# Key-HT16K23.net
KiCad netlist of a schematic drawn in Altium Designer
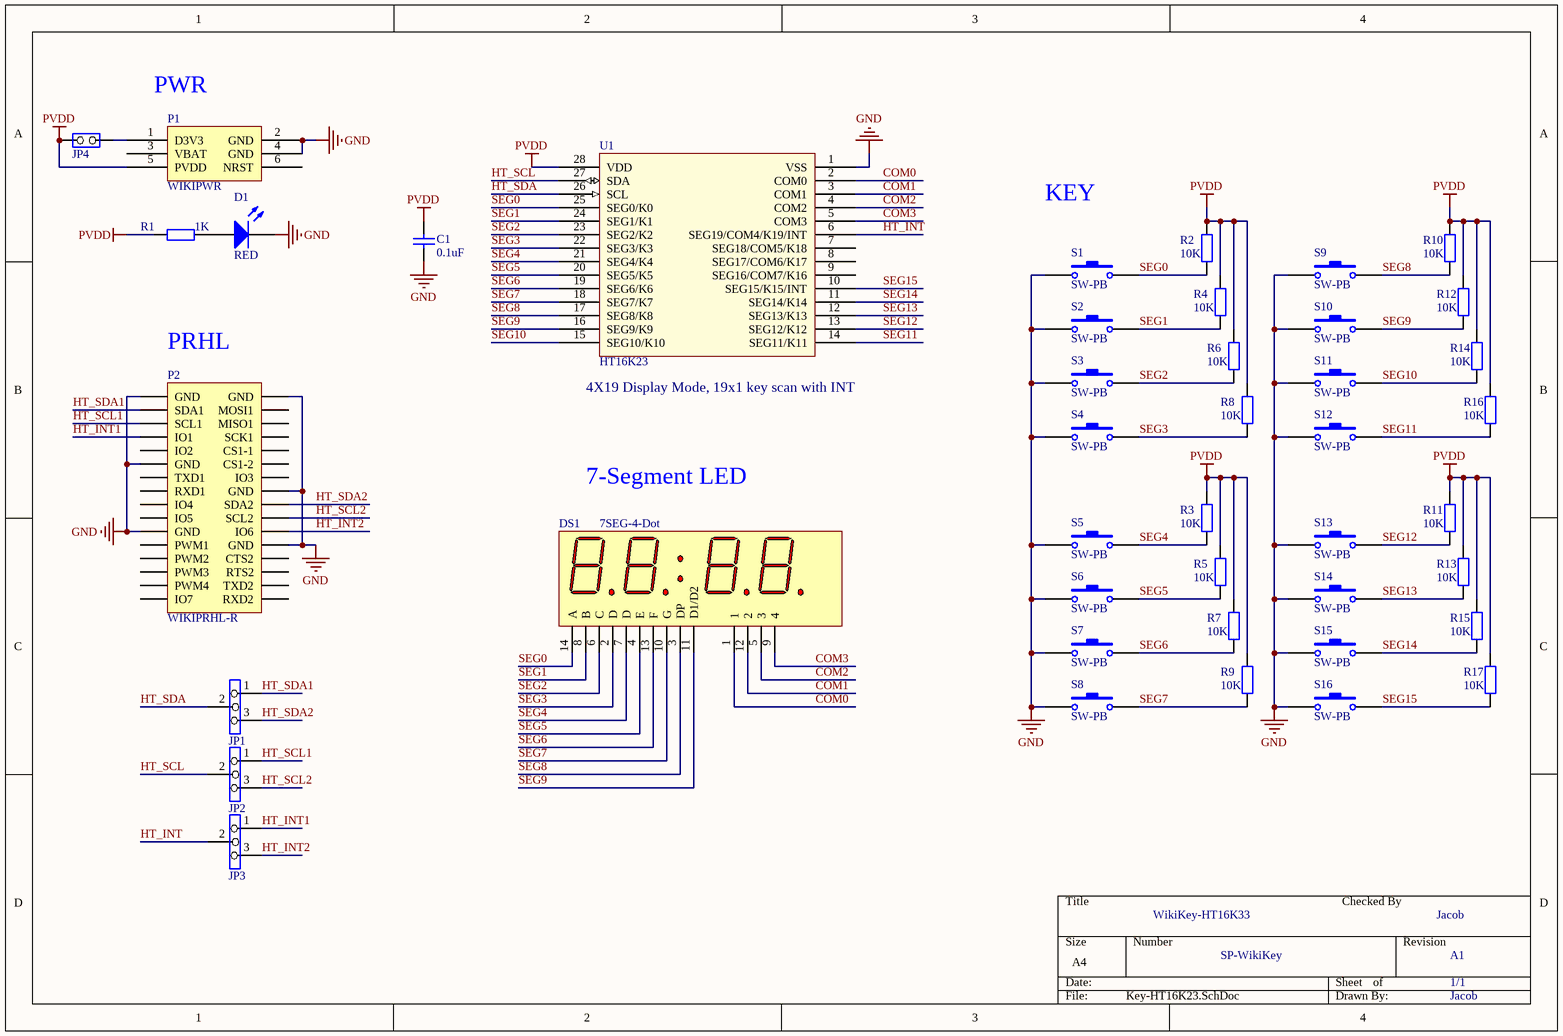
[diagram p0: Key-HT16K23.SchDoc]

(export (version "E")
  (design (tool "Eeschema 10.0.6"))
  (components
    (comp (ref "C1")
      (value "0.1uF")
      (footprint "0603M")
      (description "Capacitor")
      (fields (field (name "PUBLISHER") "Altium Limited"))
      (libsource (lib "Miscellaneous Devices") (part "Cap"))
    )
    (comp (ref "D1")
      (value "RED")
      (footprint "0603pn")
      (description "Typical INFRARED GaAs LED")
      (fields (field (name "PUBLISHER") "Altium Limited"))
      (libsource (lib "Miscellaneous Devices") (part "LED0"))
    )
    (comp (ref "DS1")
      (value "7SEG-4-Dot")
      (footprint "7SGLED-4-Dot-0.28")
      (description "Black Surface HER 7-Segment Display")
      (fields (field (name "PUBLISHER") "Altium Limited"))
      (libsource (lib "Misc") (part "7SEG-4-Dot"))
    )
    (comp (ref "JP1") (value "Jumper3") (footprint "HDR1X3/2.00mm") (libsource (lib "Misc") (part "Jumper3")))
    (comp (ref "JP2") (value "Jumper3") (footprint "HDR1X3/2.00mm") (libsource (lib "Misc") (part "Jumper3")))
    (comp (ref "JP3") (value "Jumper3") (footprint "HDR1X3/2.00mm") (libsource (lib "Misc") (part "Jumper3")))
    (comp (ref "JP4")
      (value "Jumper2-2")
      (footprint "JP2_SMD")
      (description "Jumper2")
      (libsource (lib "Misc") (part "Jumper2-2"))
    )
    (comp (ref "P1")
      (value "WIKIPWR")
      (footprint "WIKIPWR-6P")
      (description "PWR HDR")
      (libsource (lib "Connector") (part "WIKIPWR"))
    )
    (comp (ref "P2")
      (value "WIKIPRHL-R")
      (footprint "WIKIPRHL-R")
      (description "Header, 16-Pin, Dual row")
      (fields (field (name "PUBLISHER") "Altium Limited"))
      (libsource (lib "Connector") (part "WIKIPRHL-R"))
    )
    (comp (ref "R1")
      (value "1K")
      (footprint "0603M")
      (description "Resistor")
      (fields (field (name "PUBLISHER") "Altium Limited"))
      (libsource (lib "") (part "Res2_1"))
    )
    (comp (ref "R2")
      (value "10K")
      (footprint "0603M")
      (description "Resistor")
      (fields (field (name "PUBLISHER") "Altium Limited"))
      (libsource (lib "Miscellaneous Devices") (part "Res2"))
    )
    (comp (ref "R3")
      (value "10K")
      (footprint "0603M")
      (description "Resistor")
      (fields (field (name "PUBLISHER") "Altium Limited"))
      (libsource (lib "Miscellaneous Devices") (part "Res2"))
    )
    (comp (ref "R4")
      (value "10K")
      (footprint "0603M")
      (description "Resistor")
      (fields (field (name "PUBLISHER") "Altium Limited"))
      (libsource (lib "Miscellaneous Devices") (part "Res2"))
    )
    (comp (ref "R5")
      (value "10K")
      (footprint "0603M")
      (description "Resistor")
      (fields (field (name "PUBLISHER") "Altium Limited"))
      (libsource (lib "Miscellaneous Devices") (part "Res2"))
    )
    (comp (ref "R6")
      (value "10K")
      (footprint "0603M")
      (description "Resistor")
      (fields (field (name "PUBLISHER") "Altium Limited"))
      (libsource (lib "Miscellaneous Devices") (part "Res2"))
    )
    (comp (ref "R7")
      (value "10K")
      (footprint "0603M")
      (description "Resistor")
      (fields (field (name "PUBLISHER") "Altium Limited"))
      (libsource (lib "Miscellaneous Devices") (part "Res2"))
    )
    (comp (ref "R8")
      (value "10K")
      (footprint "0603M")
      (description "Resistor")
      (fields (field (name "PUBLISHER") "Altium Limited"))
      (libsource (lib "Miscellaneous Devices") (part "Res2"))
    )
    (comp (ref "R9")
      (value "10K")
      (footprint "0603M")
      (description "Resistor")
      (fields (field (name "PUBLISHER") "Altium Limited"))
      (libsource (lib "Miscellaneous Devices") (part "Res2"))
    )
    (comp (ref "R10")
      (value "10K")
      (footprint "0603M")
      (description "Resistor")
      (fields (field (name "PUBLISHER") "Altium Limited"))
      (libsource (lib "Miscellaneous Devices") (part "Res2"))
    )
    (comp (ref "R11")
      (value "10K")
      (footprint "0603M")
      (description "Resistor")
      (fields (field (name "PUBLISHER") "Altium Limited"))
      (libsource (lib "Miscellaneous Devices") (part "Res2"))
    )
    (comp (ref "R12")
      (value "10K")
      (footprint "0603M")
      (description "Resistor")
      (fields (field (name "PUBLISHER") "Altium Limited"))
      (libsource (lib "Miscellaneous Devices") (part "Res2"))
    )
    (comp (ref "R13")
      (value "10K")
      (footprint "0603M")
      (description "Resistor")
      (fields (field (name "PUBLISHER") "Altium Limited"))
      (libsource (lib "Miscellaneous Devices") (part "Res2"))
    )
    (comp (ref "R14")
      (value "10K")
      (footprint "0603M")
      (description "Resistor")
      (fields (field (name "PUBLISHER") "Altium Limited"))
      (libsource (lib "Miscellaneous Devices") (part "Res2"))
    )
    (comp (ref "R15")
      (value "10K")
      (footprint "0603M")
      (description "Resistor")
      (fields (field (name "PUBLISHER") "Altium Limited"))
      (libsource (lib "Miscellaneous Devices") (part "Res2"))
    )
    (comp (ref "R16")
      (value "10K")
      (footprint "0603M")
      (description "Resistor")
      (fields (field (name "PUBLISHER") "Altium Limited"))
      (libsource (lib "Miscellaneous Devices") (part "Res2"))
    )
    (comp (ref "R17")
      (value "10K")
      (footprint "0603M")
      (description "Resistor")
      (fields (field (name "PUBLISHER") "Altium Limited"))
      (libsource (lib "Miscellaneous Devices") (part "Res2"))
    )
    (comp (ref "S1")
      (value "SW-PB")
      (footprint "KEY-4.5X4.5-SMD")
      (description "Switch")
      (fields (field (name "PUBLISHER") "Altium Limited"))
      (libsource (lib "CT107D_SUDA") (part "SW-PB"))
    )
    (comp (ref "S2")
      (value "SW-PB")
      (footprint "KEY-4.5X4.5-SMD")
      (description "Switch")
      (fields (field (name "PUBLISHER") "Altium Limited"))
      (libsource (lib "CT107D_SUDA") (part "SW-PB"))
    )
    (comp (ref "S3")
      (value "SW-PB")
      (footprint "KEY-4.5X4.5-SMD")
      (description "Switch")
      (fields (field (name "PUBLISHER") "Altium Limited"))
      (libsource (lib "CT107D_SUDA") (part "SW-PB"))
    )
    (comp (ref "S4")
      (value "SW-PB")
      (footprint "KEY-4.5X4.5-SMD")
      (description "Switch")
      (fields (field (name "PUBLISHER") "Altium Limited"))
      (libsource (lib "CT107D_SUDA") (part "SW-PB"))
    )
    (comp (ref "S5")
      (value "SW-PB")
      (footprint "KEY-4.5X4.5-SMD")
      (description "Switch")
      (fields (field (name "PUBLISHER") "Altium Limited"))
      (libsource (lib "CT107D_SUDA") (part "SW-PB"))
    )
    (comp (ref "S6")
      (value "SW-PB")
      (footprint "KEY-4.5X4.5-SMD")
      (description "Switch")
      (fields (field (name "PUBLISHER") "Altium Limited"))
      (libsource (lib "CT107D_SUDA") (part "SW-PB"))
    )
    (comp (ref "S7")
      (value "SW-PB")
      (footprint "KEY-4.5X4.5-SMD")
      (description "Switch")
      (fields (field (name "PUBLISHER") "Altium Limited"))
      (libsource (lib "CT107D_SUDA") (part "SW-PB"))
    )
    (comp (ref "S8")
      (value "SW-PB")
      (footprint "KEY-4.5X4.5-SMD")
      (description "Switch")
      (fields (field (name "PUBLISHER") "Altium Limited"))
      (libsource (lib "CT107D_SUDA") (part "SW-PB"))
    )
    (comp (ref "S9")
      (value "SW-PB")
      (footprint "KEY-4.5X4.5-SMD")
      (description "Switch")
      (fields (field (name "PUBLISHER") "Altium Limited"))
      (libsource (lib "CT107D_SUDA") (part "SW-PB"))
    )
    (comp (ref "S10")
      (value "SW-PB")
      (footprint "KEY-4.5X4.5-SMD")
      (description "Switch")
      (fields (field (name "PUBLISHER") "Altium Limited"))
      (libsource (lib "CT107D_SUDA") (part "SW-PB"))
    )
    (comp (ref "S11")
      (value "SW-PB")
      (footprint "KEY-4.5X4.5-SMD")
      (description "Switch")
      (fields (field (name "PUBLISHER") "Altium Limited"))
      (libsource (lib "CT107D_SUDA") (part "SW-PB"))
    )
    (comp (ref "S12")
      (value "SW-PB")
      (footprint "KEY-4.5X4.5-SMD")
      (description "Switch")
      (fields (field (name "PUBLISHER") "Altium Limited"))
      (libsource (lib "CT107D_SUDA") (part "SW-PB"))
    )
    (comp (ref "S13")
      (value "SW-PB")
      (footprint "KEY-4.5X4.5-SMD")
      (description "Switch")
      (fields (field (name "PUBLISHER") "Altium Limited"))
      (libsource (lib "CT107D_SUDA") (part "SW-PB"))
    )
    (comp (ref "S14")
      (value "SW-PB")
      (footprint "KEY-4.5X4.5-SMD")
      (description "Switch")
      (fields (field (name "PUBLISHER") "Altium Limited"))
      (libsource (lib "CT107D_SUDA") (part "SW-PB"))
    )
    (comp (ref "S15")
      (value "SW-PB")
      (footprint "KEY-4.5X4.5-SMD")
      (description "Switch")
      (fields (field (name "PUBLISHER") "Altium Limited"))
      (libsource (lib "CT107D_SUDA") (part "SW-PB"))
    )
    (comp (ref "S16")
      (value "SW-PB")
      (footprint "KEY-4.5X4.5-SMD")
      (description "Switch")
      (fields (field (name "PUBLISHER") "Altium Limited"))
      (libsource (lib "CT107D_SUDA") (part "SW-PB"))
    )
    (comp (ref "U1")
      (value "HT16K23")
      (footprint "SO28_M")
      (description "LCD Driver with keyscan")
      (libsource (lib "Logic") (part "HT16K23"))
    )
  )
  (nets
    (net (code "1") (name "/COM0") (class "Default")
      (node (ref "DS1") (pin "1") (pinfunction "1_1") (pintype "passive"))
      (node (ref "U1") (pin "2") (pinfunction "COM0_2") (pintype "passive"))
    )
    (net (code "2") (name "/COM1") (class "Default")
      (node (ref "DS1") (pin "12") (pinfunction "2_12") (pintype "passive"))
      (node (ref "U1") (pin "3") (pinfunction "COM1_3") (pintype "passive"))
    )
    (net (code "3") (name "/COM2") (class "Default")
      (node (ref "DS1") (pin "5") (pinfunction "3_5") (pintype "passive"))
      (node (ref "U1") (pin "4") (pinfunction "COM2_4") (pintype "passive"))
    )
    (net (code "4") (name "/COM3") (class "Default")
      (node (ref "DS1") (pin "9") (pinfunction "4_9") (pintype "passive"))
      (node (ref "U1") (pin "5") (pinfunction "COM3_5") (pintype "passive"))
    )
    (net (code "5") (name "/HT_INT") (class "Default")
      (node (ref "JP3") (pin "2") (pintype "passive"))
      (node (ref "U1") (pin "6") (pinfunction "SEG19/COM4/K19/INT_6") (pintype "passive"))
    )
    (net (code "6") (name "/HT_INT1") (class "Default")
      (node (ref "JP3") (pin "1") (pintype "passive"))
      (node (ref "P2") (pin "7") (pinfunction "IO1_7") (pintype "passive"))
    )
    (net (code "7") (name "/HT_INT2") (class "Default")
      (node (ref "JP3") (pin "3") (pintype "passive"))
      (node (ref "P2") (pin "22") (pinfunction "IO6_22") (pintype "passive"))
    )
    (net (code "8") (name "/HT_SCL") (class "Default")
      (node (ref "JP2") (pin "2") (pintype "passive"))
      (node (ref "U1") (pin "27") (pinfunction "SDA_27") (pintype "bidirectional"))
    )
    (net (code "9") (name "/HT_SCL1") (class "Default")
      (node (ref "JP2") (pin "1") (pintype "passive"))
      (node (ref "P2") (pin "5") (pinfunction "SCL1_5") (pintype "passive"))
    )
    (net (code "10") (name "/HT_SCL2") (class "Default")
      (node (ref "JP2") (pin "3") (pintype "passive"))
      (node (ref "P2") (pin "20") (pinfunction "SCL2_20") (pintype "passive"))
    )
    (net (code "11") (name "/HT_SDA") (class "Default")
      (node (ref "JP1") (pin "2") (pintype "passive"))
      (node (ref "U1") (pin "26") (pinfunction "SCL_26") (pintype "input"))
    )
    (net (code "12") (name "/HT_SDA1") (class "Default")
      (node (ref "JP1") (pin "1") (pintype "passive"))
      (node (ref "P2") (pin "3") (pinfunction "SDA1_3") (pintype "passive"))
    )
    (net (code "13") (name "/HT_SDA2") (class "Default")
      (node (ref "JP1") (pin "3") (pintype "passive"))
      (node (ref "P2") (pin "18") (pinfunction "SDA2_18") (pintype "passive"))
    )
    (net (code "14") (name "/SEG0") (class "Default")
      (node (ref "DS1") (pin "14") (pinfunction "A_14") (pintype "passive"))
      (node (ref "R2") (pin "2") (pinfunction "2_2") (pintype "passive"))
      (node (ref "S1") (pin "2") (pinfunction "2_2") (pintype "passive"))
      (node (ref "U1") (pin "25") (pinfunction "SEG0/K0_25") (pintype "passive"))
    )
    (net (code "15") (name "/SEG1") (class "Default")
      (node (ref "DS1") (pin "8") (pinfunction "B_8") (pintype "passive"))
      (node (ref "R4") (pin "2") (pinfunction "2_2") (pintype "passive"))
      (node (ref "S2") (pin "2") (pinfunction "2_2") (pintype "passive"))
      (node (ref "U1") (pin "24") (pinfunction "SEG1/K1_24") (pintype "passive"))
    )
    (net (code "16") (name "/SEG2") (class "Default")
      (node (ref "DS1") (pin "6") (pinfunction "C_6") (pintype "passive"))
      (node (ref "R6") (pin "2") (pinfunction "2_2") (pintype "passive"))
      (node (ref "S3") (pin "2") (pinfunction "2_2") (pintype "passive"))
      (node (ref "U1") (pin "23") (pinfunction "SEG2/K2_23") (pintype "passive"))
    )
    (net (code "17") (name "/SEG3") (class "Default")
      (node (ref "DS1") (pin "2") (pinfunction "D_2") (pintype "passive"))
      (node (ref "R8") (pin "2") (pinfunction "2_2") (pintype "passive"))
      (node (ref "S4") (pin "2") (pinfunction "2_2") (pintype "passive"))
      (node (ref "U1") (pin "22") (pinfunction "SEG3/K3_22") (pintype "passive"))
    )
    (net (code "18") (name "/SEG4") (class "Default")
      (node (ref "DS1") (pin "7") (pinfunction "D_7") (pintype "passive"))
      (node (ref "R3") (pin "2") (pinfunction "2_2") (pintype "passive"))
      (node (ref "S5") (pin "2") (pinfunction "2_2") (pintype "passive"))
      (node (ref "U1") (pin "21") (pinfunction "SEG4/K4_21") (pintype "passive"))
    )
    (net (code "19") (name "/SEG5") (class "Default")
      (node (ref "DS1") (pin "4") (pinfunction "E_4") (pintype "passive"))
      (node (ref "R5") (pin "2") (pinfunction "2_2") (pintype "passive"))
      (node (ref "S6") (pin "2") (pinfunction "2_2") (pintype "passive"))
      (node (ref "U1") (pin "20") (pinfunction "SEG5/K5_20") (pintype "passive"))
    )
    (net (code "20") (name "/SEG6") (class "Default")
      (node (ref "DS1") (pin "13") (pinfunction "F_13") (pintype "passive"))
      (node (ref "R7") (pin "2") (pinfunction "2_2") (pintype "passive"))
      (node (ref "S7") (pin "2") (pinfunction "2_2") (pintype "passive"))
      (node (ref "U1") (pin "19") (pinfunction "SEG6/K6_19") (pintype "passive"))
    )
    (net (code "21") (name "/SEG7") (class "Default")
      (node (ref "DS1") (pin "10") (pinfunction "G_10") (pintype "passive"))
      (node (ref "R9") (pin "2") (pinfunction "2_2") (pintype "passive"))
      (node (ref "S8") (pin "2") (pinfunction "2_2") (pintype "passive"))
      (node (ref "U1") (pin "18") (pinfunction "SEG7/K7_18") (pintype "passive"))
    )
    (net (code "22") (name "/SEG8") (class "Default")
      (node (ref "DS1") (pin "3") (pinfunction "DP_3") (pintype "passive"))
      (node (ref "R10") (pin "2") (pinfunction "2_2") (pintype "passive"))
      (node (ref "S9") (pin "2") (pinfunction "2_2") (pintype "passive"))
      (node (ref "U1") (pin "17") (pinfunction "SEG8/K8_17") (pintype "passive"))
    )
    (net (code "23") (name "/SEG9") (class "Default")
      (node (ref "DS1") (pin "11") (pinfunction "D1/D2_11") (pintype "passive"))
      (node (ref "R12") (pin "2") (pinfunction "2_2") (pintype "passive"))
      (node (ref "S10") (pin "2") (pinfunction "2_2") (pintype "passive"))
      (node (ref "U1") (pin "16") (pinfunction "SEG9/K9_16") (pintype "passive"))
    )
    (net (code "24") (name "/SEG10") (class "Default")
      (node (ref "R14") (pin "2") (pinfunction "2_2") (pintype "passive"))
      (node (ref "S11") (pin "2") (pinfunction "2_2") (pintype "passive"))
      (node (ref "U1") (pin "15") (pinfunction "SEG10/K10_15") (pintype "passive"))
    )
    (net (code "25") (name "/SEG11") (class "Default")
      (node (ref "R16") (pin "2") (pinfunction "2_2") (pintype "passive"))
      (node (ref "S12") (pin "2") (pinfunction "2_2") (pintype "passive"))
      (node (ref "U1") (pin "14") (pinfunction "SEG11/K11_14") (pintype "passive"))
    )
    (net (code "26") (name "/SEG12") (class "Default")
      (node (ref "R11") (pin "2") (pinfunction "2_2") (pintype "passive"))
      (node (ref "S13") (pin "2") (pinfunction "2_2") (pintype "passive"))
      (node (ref "U1") (pin "13") (pinfunction "SEG12/K12_13") (pintype "passive"))
    )
    (net (code "27") (name "/SEG13") (class "Default")
      (node (ref "R13") (pin "2") (pinfunction "2_2") (pintype "passive"))
      (node (ref "S14") (pin "2") (pinfunction "2_2") (pintype "passive"))
      (node (ref "U1") (pin "12") (pinfunction "SEG13/K13_12") (pintype "passive"))
    )
    (net (code "28") (name "/SEG14") (class "Default")
      (node (ref "R15") (pin "2") (pinfunction "2_2") (pintype "passive"))
      (node (ref "S15") (pin "2") (pinfunction "2_2") (pintype "passive"))
      (node (ref "U1") (pin "11") (pinfunction "SEG14/K14_11") (pintype "passive"))
    )
    (net (code "29") (name "/SEG15") (class "Default")
      (node (ref "R17") (pin "2") (pinfunction "2_2") (pintype "passive"))
      (node (ref "S16") (pin "2") (pinfunction "2_2") (pintype "passive"))
      (node (ref "U1") (pin "10") (pinfunction "SEG15/K15/INT_10") (pintype "passive"))
    )
    (net (code "30") (name "GND") (class "Default")
      (node (ref "C1") (pin "1") (pinfunction "1_1") (pintype "passive"))
      (node (ref "D1") (pin "2") (pinfunction "K_2") (pintype "passive"))
      (node (ref "P1") (pin "2") (pinfunction "GND_2") (pintype "passive"))
      (node (ref "P1") (pin "4") (pinfunction "GND_4") (pintype "passive"))
      (node (ref "P2") (pin "1") (pinfunction "GND_1") (pintype "passive"))
      (node (ref "P2") (pin "11") (pinfunction "GND_11") (pintype "passive"))
      (node (ref "P2") (pin "16") (pinfunction "GND_16") (pintype "passive"))
      (node (ref "P2") (pin "2") (pinfunction "GND_2") (pintype "passive"))
      (node (ref "P2") (pin "21") (pinfunction "GND_21") (pintype "passive"))
      (node (ref "P2") (pin "24") (pinfunction "GND_24") (pintype "passive"))
      (node (ref "S1") (pin "1") (pinfunction "1_1") (pintype "passive"))
      (node (ref "S10") (pin "1") (pinfunction "1_1") (pintype "passive"))
      (node (ref "S11") (pin "1") (pinfunction "1_1") (pintype "passive"))
      (node (ref "S12") (pin "1") (pinfunction "1_1") (pintype "passive"))
      (node (ref "S13") (pin "1") (pinfunction "1_1") (pintype "passive"))
      (node (ref "S14") (pin "1") (pinfunction "1_1") (pintype "passive"))
      (node (ref "S15") (pin "1") (pinfunction "1_1") (pintype "passive"))
      (node (ref "S16") (pin "1") (pinfunction "1_1") (pintype "passive"))
      (node (ref "S2") (pin "1") (pinfunction "1_1") (pintype "passive"))
      (node (ref "S3") (pin "1") (pinfunction "1_1") (pintype "passive"))
      (node (ref "S4") (pin "1") (pinfunction "1_1") (pintype "passive"))
      (node (ref "S5") (pin "1") (pinfunction "1_1") (pintype "passive"))
      (node (ref "S6") (pin "1") (pinfunction "1_1") (pintype "passive"))
      (node (ref "S7") (pin "1") (pinfunction "1_1") (pintype "passive"))
      (node (ref "S8") (pin "1") (pinfunction "1_1") (pintype "passive"))
      (node (ref "S9") (pin "1") (pinfunction "1_1") (pintype "passive"))
      (node (ref "U1") (pin "1") (pinfunction "VSS_1") (pintype "power_in"))
    )
    (net (code "31") (name "Net-(D1-A)") (class "Default")
      (node (ref "D1") (pin "1") (pinfunction "A_1") (pintype "passive"))
      (node (ref "R1") (pin "1") (pinfunction "1_1") (pintype "passive"))
    )
    (net (code "32") (name "Net-(JP4-COMMON)") (class "Default")
      (node (ref "JP4") (pin "1") (pinfunction "COMMON_1") (pintype "passive"))
      (node (ref "P1") (pin "1") (pinfunction "D3V3_1") (pintype "passive"))
    )
    (net (code "33") (name "PVDD") (class "Default")
      (node (ref "C1") (pin "2") (pinfunction "2_2") (pintype "passive"))
      (node (ref "JP4") (pin "2") (pinfunction "NO_2") (pintype "passive"))
      (node (ref "P1") (pin "5") (pinfunction "PVDD_5") (pintype "passive"))
      (node (ref "R1") (pin "2") (pinfunction "2_2") (pintype "passive"))
      (node (ref "R10") (pin "1") (pinfunction "1_1") (pintype "passive"))
      (node (ref "R11") (pin "1") (pinfunction "1_1") (pintype "passive"))
      (node (ref "R12") (pin "1") (pinfunction "1_1") (pintype "passive"))
      (node (ref "R13") (pin "1") (pinfunction "1_1") (pintype "passive"))
      (node (ref "R14") (pin "1") (pinfunction "1_1") (pintype "passive"))
      (node (ref "R15") (pin "1") (pinfunction "1_1") (pintype "passive"))
      (node (ref "R16") (pin "1") (pinfunction "1_1") (pintype "passive"))
      (node (ref "R17") (pin "1") (pinfunction "1_1") (pintype "passive"))
      (node (ref "R2") (pin "1") (pinfunction "1_1") (pintype "passive"))
      (node (ref "R3") (pin "1") (pinfunction "1_1") (pintype "passive"))
      (node (ref "R4") (pin "1") (pinfunction "1_1") (pintype "passive"))
      (node (ref "R5") (pin "1") (pinfunction "1_1") (pintype "passive"))
      (node (ref "R6") (pin "1") (pinfunction "1_1") (pintype "passive"))
      (node (ref "R7") (pin "1") (pinfunction "1_1") (pintype "passive"))
      (node (ref "R8") (pin "1") (pinfunction "1_1") (pintype "passive"))
      (node (ref "R9") (pin "1") (pinfunction "1_1") (pintype "passive"))
      (node (ref "U1") (pin "28") (pinfunction "VDD_28") (pintype "power_in"))
    )
    (net (code "34") (name "unconnected-(P1-NRST-Pad6)") (class "Default")
      (node (ref "P1") (pin "6") (pinfunction "NRST_6") (pintype "passive"))
    )
    (net (code "35") (name "unconnected-(P1-VBAT-Pad3)") (class "Default")
      (node (ref "P1") (pin "3") (pinfunction "VBAT_3") (pintype "passive"))
    )
    (net (code "36") (name "unconnected-(P2-CS1-1-Pad10)") (class "Default")
      (node (ref "P2") (pin "10") (pinfunction "CS1-1_10") (pintype "passive"))
    )
    (net (code "37") (name "unconnected-(P2-CS1-2-Pad12)") (class "Default")
      (node (ref "P2") (pin "12") (pinfunction "CS1-2_12") (pintype "passive"))
    )
    (net (code "38") (name "unconnected-(P2-CTS2-Pad26)") (class "Default")
      (node (ref "P2") (pin "26") (pinfunction "CTS2_26") (pintype "passive"))
    )
    (net (code "39") (name "unconnected-(P2-IO2-Pad9)") (class "Default")
      (node (ref "P2") (pin "9") (pinfunction "IO2_9") (pintype "passive"))
    )
    (net (code "40") (name "unconnected-(P2-IO3-Pad14)") (class "Default")
      (node (ref "P2") (pin "14") (pinfunction "IO3_14") (pintype "passive"))
    )
    (net (code "41") (name "unconnected-(P2-IO4-Pad17)") (class "Default")
      (node (ref "P2") (pin "17") (pinfunction "IO4_17") (pintype "passive"))
    )
    (net (code "42") (name "unconnected-(P2-IO5-Pad19)") (class "Default")
      (node (ref "P2") (pin "19") (pinfunction "IO5_19") (pintype "passive"))
    )
    (net (code "43") (name "unconnected-(P2-IO7-Pad31)") (class "Default")
      (node (ref "P2") (pin "31") (pinfunction "IO7_31") (pintype "passive"))
    )
    (net (code "44") (name "unconnected-(P2-MISO1-Pad6)") (class "Default")
      (node (ref "P2") (pin "6") (pinfunction "MISO1_6") (pintype "passive"))
    )
    (net (code "45") (name "unconnected-(P2-MOSI1-Pad4)") (class "Default")
      (node (ref "P2") (pin "4") (pinfunction "MOSI1_4") (pintype "passive"))
    )
    (net (code "46") (name "unconnected-(P2-PWM1-Pad23)") (class "Default")
      (node (ref "P2") (pin "23") (pinfunction "PWM1_23") (pintype "passive"))
    )
    (net (code "47") (name "unconnected-(P2-PWM2-Pad25)") (class "Default")
      (node (ref "P2") (pin "25") (pinfunction "PWM2_25") (pintype "passive"))
    )
    (net (code "48") (name "unconnected-(P2-PWM3-Pad27)") (class "Default")
      (node (ref "P2") (pin "27") (pinfunction "PWM3_27") (pintype "passive"))
    )
    (net (code "49") (name "unconnected-(P2-PWM4-Pad29)") (class "Default")
      (node (ref "P2") (pin "29") (pinfunction "PWM4_29") (pintype "passive"))
    )
    (net (code "50") (name "unconnected-(P2-RTS2-Pad28)") (class "Default")
      (node (ref "P2") (pin "28") (pinfunction "RTS2_28") (pintype "passive"))
    )
    (net (code "51") (name "unconnected-(P2-RXD1-Pad15)") (class "Default")
      (node (ref "P2") (pin "15") (pinfunction "RXD1_15") (pintype "passive"))
    )
    (net (code "52") (name "unconnected-(P2-RXD2-Pad32)") (class "Default")
      (node (ref "P2") (pin "32") (pinfunction "RXD2_32") (pintype "passive"))
    )
    (net (code "53") (name "unconnected-(P2-SCK1-Pad8)") (class "Default")
      (node (ref "P2") (pin "8") (pinfunction "SCK1_8") (pintype "passive"))
    )
    (net (code "54") (name "unconnected-(P2-TXD1-Pad13)") (class "Default")
      (node (ref "P2") (pin "13") (pinfunction "TXD1_13") (pintype "passive"))
    )
    (net (code "55") (name "unconnected-(P2-TXD2-Pad30)") (class "Default")
      (node (ref "P2") (pin "30") (pinfunction "TXD2_30") (pintype "passive"))
    )
    (net (code "56") (name "unconnected-(U1-SEG16{slash}COM7{slash}K16-Pad9)") (class "Default")
      (node (ref "U1") (pin "9") (pinfunction "SEG16/COM7/K16_9") (pintype "passive"))
    )
    (net (code "57") (name "unconnected-(U1-SEG17{slash}COM6{slash}K17-Pad8)") (class "Default")
      (node (ref "U1") (pin "8") (pinfunction "SEG17/COM6/K17_8") (pintype "passive"))
    )
    (net (code "58") (name "unconnected-(U1-SEG18{slash}COM5{slash}K18-Pad7)") (class "Default")
      (node (ref "U1") (pin "7") (pinfunction "SEG18/COM5/K18_7") (pintype "passive"))
    )
  )
)
